# DFSDM.net
KiCad netlist of a schematic drawn in Altium Designer
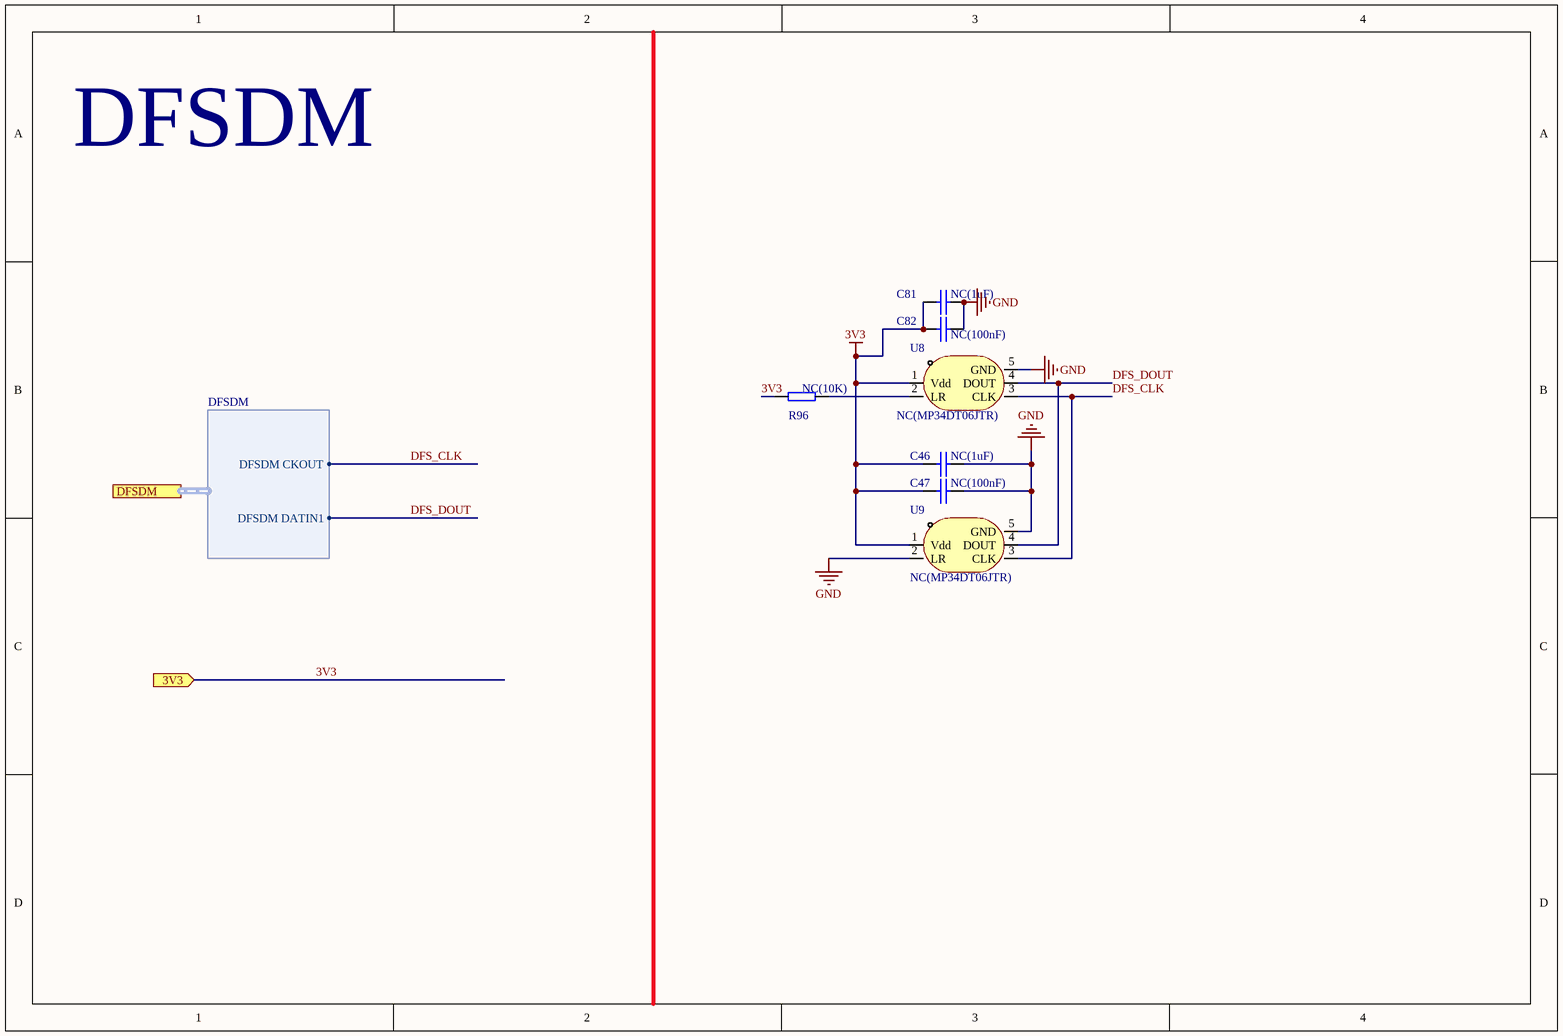
[diagram p0: DFSDM.SchDoc]

(export (version "E")
  (design (tool "Eeschema 10.0.6"))
  (components
    (comp (ref "C46")
      (value "NC(1uF)")
      (footprint "0402_C")
      (description "Capacitor")
      (libsource (lib "*") (part "CAP"))
    )
    (comp (ref "C47")
      (value "NC(100nF)")
      (footprint "0402_C")
      (description "Capacitor")
      (libsource (lib "*") (part "CAP"))
    )
    (comp (ref "C81")
      (value "NC(1uF)")
      (footprint "0402_C")
      (description "Capacitor")
      (libsource (lib "*") (part "CAP"))
    )
    (comp (ref "C82")
      (value "NC(100nF)")
      (footprint "0402_C")
      (description "Capacitor")
      (libsource (lib "*") (part "CAP"))
    )
    (comp (ref "R96") (value "NC(10K)") (footprint "0402") (libsource (lib "*") (part "RES")))
    (comp (ref "U8")
      (value "NC(MP34DT06JTR)")
      (footprint "MIC-MP34DT06J-L3.0-W4.0-P0.85-1.35-BL")
      (libsource (lib "wch_sch_others") (part "MP34DT06JTR"))
    )
    (comp (ref "U9")
      (value "NC(MP34DT06JTR)")
      (footprint "MIC-MP34DT06J-L3.0-W4.0-P0.85-1.35-BL")
      (libsource (lib "wch_sch_others") (part "MP34DT06JTR"))
    )
  )
  (nets
    (net (code "2") (name "/DFS_CLK") (class "Default")
      (node (ref "U8") (pin "3") (pinfunction "CLK_3") (pintype "passive"))
      (node (ref "U9") (pin "3") (pinfunction "CLK_3") (pintype "passive"))
    )
    (net (code "3") (name "/DFS_DOUT") (class "Default")
      (node (ref "U8") (pin "4") (pinfunction "DOUT_4") (pintype "passive"))
      (node (ref "U9") (pin "4") (pinfunction "DOUT_4") (pintype "passive"))
    )
    (net (code "5") (name "3V3") (class "Default")
      (node (ref "C46") (pin "2") (pinfunction "2_2") (pintype "passive"))
      (node (ref "C47") (pin "2") (pinfunction "2_2") (pintype "passive"))
      (node (ref "C81") (pin "2") (pinfunction "2_2") (pintype "passive"))
      (node (ref "C82") (pin "2") (pinfunction "2_2") (pintype "passive"))
      (node (ref "R96") (pin "2") (pintype "passive"))
      (node (ref "U8") (pin "1") (pinfunction "Vdd_1") (pintype "passive"))
      (node (ref "U9") (pin "1") (pinfunction "Vdd_1") (pintype "passive"))
    )
    (net (code "6") (name "GND") (class "Default")
      (node (ref "C46") (pin "1") (pinfunction "1_1") (pintype "passive"))
      (node (ref "C47") (pin "1") (pinfunction "1_1") (pintype "passive"))
      (node (ref "C81") (pin "1") (pinfunction "1_1") (pintype "passive"))
      (node (ref "C82") (pin "1") (pinfunction "1_1") (pintype "passive"))
      (node (ref "U8") (pin "5") (pinfunction "GND_5") (pintype "passive"))
      (node (ref "U9") (pin "2") (pinfunction "LR_2") (pintype "passive"))
      (node (ref "U9") (pin "5") (pinfunction "GND_5") (pintype "passive"))
    )
    (net (code "7") (name "Net-(U8-LR)") (class "Default")
      (node (ref "R96") (pin "1") (pintype "passive"))
      (node (ref "U8") (pin "2") (pinfunction "LR_2") (pintype "passive"))
    )
  )
)
